# sensor_module_base.net
KiCad netlist of a schematic drawn in EAGLE
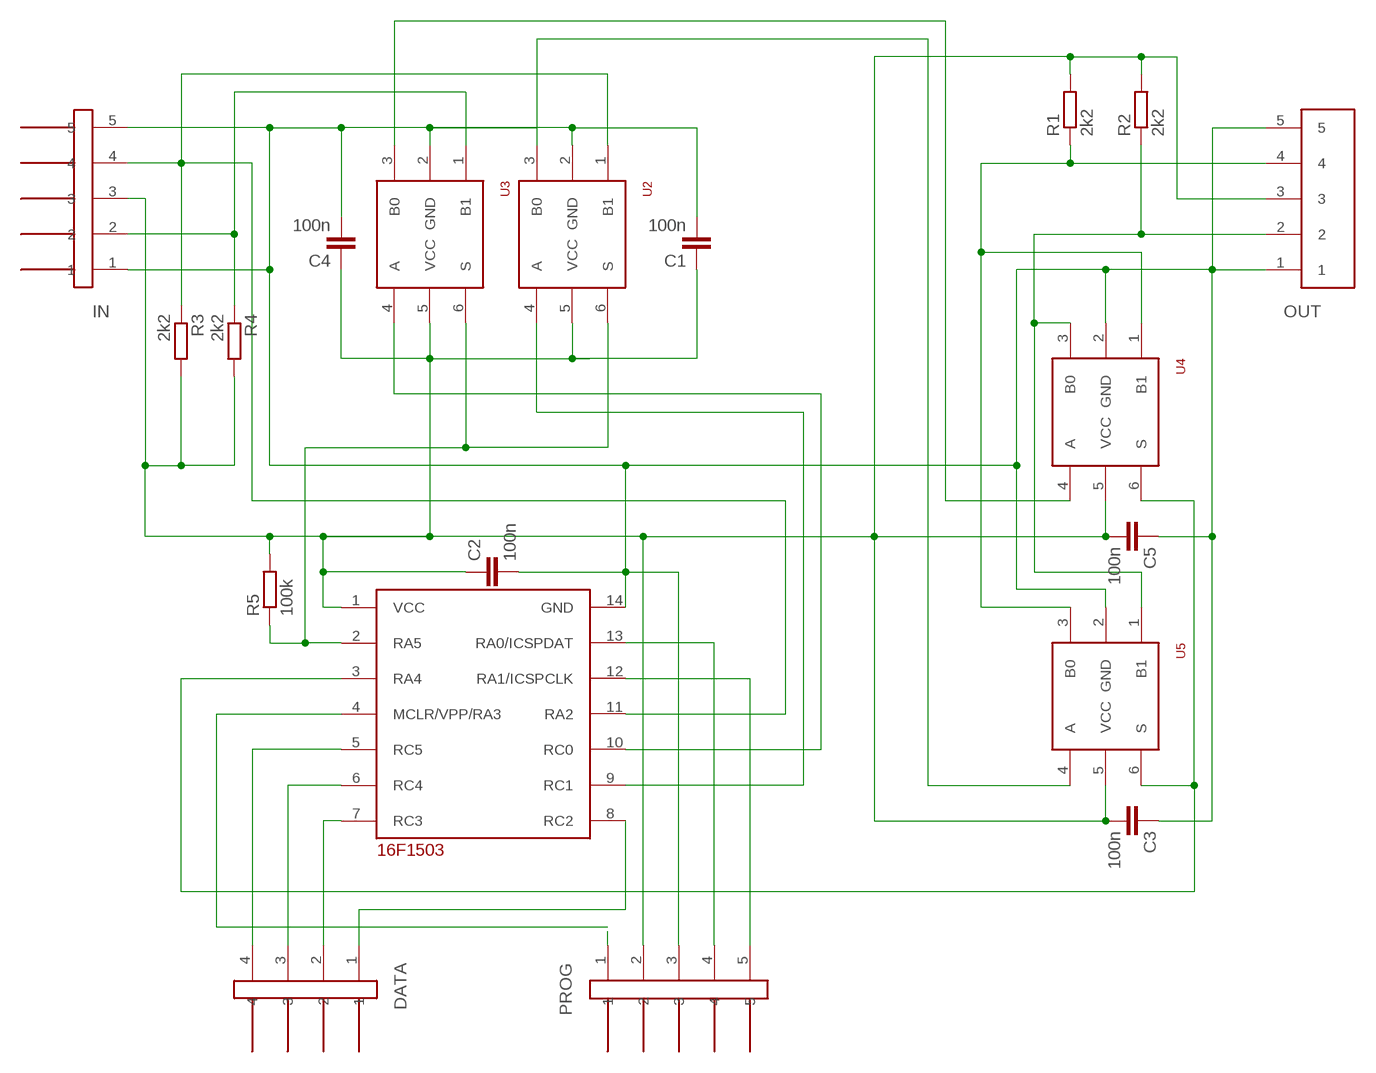
[diagram p0: schematic, sheet 1]

(export (version "E")
  (design (tool "Eeschema 10.0.6"))
  (components
    (comp (ref "C1")
      (value "100n")
      (footprint "eagle-import:C0603K")
      (libsource (lib "eagle-import") (part "C-EUC0603K"))
    )
    (comp (ref "C2")
      (value "100n")
      (footprint "eagle-import:C0603K")
      (libsource (lib "eagle-import") (part "C-EUC0603K"))
    )
    (comp (ref "C3")
      (value "100n")
      (footprint "eagle-import:C0603K")
      (libsource (lib "eagle-import") (part "C-EUC0603K"))
    )
    (comp (ref "C4")
      (value "100n")
      (footprint "eagle-import:C0603K")
      (libsource (lib "eagle-import") (part "C-EUC0603K"))
    )
    (comp (ref "C5")
      (value "100n")
      (footprint "eagle-import:C0603K")
      (libsource (lib "eagle-import") (part "C-EUC0603K"))
    )
    (comp (ref "DATA")
      (value "JUMPER4M")
      (footprint "eagle-import:JUMPER4M")
      (libsource (lib "eagle-import") (part "JUMPER4M"))
    )
    (comp (ref "IN")
      (value "JUMPER5M-90")
      (footprint "eagle-import:JUMPER5M-90")
      (libsource (lib "eagle-import") (part "JUMPER5M-90"))
    )
    (comp (ref "OUT")
      (value "JUMPER5F-90")
      (footprint "eagle-import:JUMPER5F-90")
      (libsource (lib "eagle-import") (part "JUMPER5F-90"))
    )
    (comp (ref "PROG")
      (value "JUMPER5M")
      (footprint "eagle-import:JUMPER5M")
      (libsource (lib "eagle-import") (part "JUMPER5M"))
    )
    (comp (ref "R1")
      (value "2k2")
      (footprint "eagle-import:R0603")
      (libsource (lib "eagle-import") (part "R-EU_R0603"))
    )
    (comp (ref "R2")
      (value "2k2")
      (footprint "eagle-import:R0603")
      (libsource (lib "eagle-import") (part "R-EU_R0603"))
    )
    (comp (ref "R3")
      (value "2k2")
      (footprint "eagle-import:R0603")
      (libsource (lib "eagle-import") (part "R-EU_R0603"))
    )
    (comp (ref "R4")
      (value "2k2")
      (footprint "eagle-import:R0603")
      (libsource (lib "eagle-import") (part "R-EU_R0603"))
    )
    (comp (ref "R5")
      (value "100k")
      (footprint "eagle-import:R0603")
      (libsource (lib "eagle-import") (part "R-EU_R0603"))
    )
    (comp (ref "U1")
      (value "16F1503")
      (footprint "eagle-import:TSSOP14")
      (libsource (lib "eagle-import") (part "16F103-TSSOP"))
    )
    (comp (ref "U2")
      (value "NC7SB3157P6X")
      (footprint "eagle-import:SC70-6L")
      (libsource (lib "eagle-import") (part "NC7SB3157P6X"))
    )
    (comp (ref "U3")
      (value "NC7SB3157P6X")
      (footprint "eagle-import:SC70-6L")
      (libsource (lib "eagle-import") (part "NC7SB3157P6X"))
    )
    (comp (ref "U4")
      (value "NC7SB3157P6X")
      (footprint "eagle-import:SC70-6L")
      (libsource (lib "eagle-import") (part "NC7SB3157P6X"))
    )
    (comp (ref "U5")
      (value "NC7SB3157P6X")
      (footprint "eagle-import:SC70-6L")
      (libsource (lib "eagle-import") (part "NC7SB3157P6X"))
    )
  )
  (nets
    (net (code "1") (name "Net-(U1-GND)") (class "Default")
      (node (ref "C1") (pin "2") (pinfunction "2_2") (pintype "passive"))
      (node (ref "C2") (pin "2") (pinfunction "2_2") (pintype "passive"))
      (node (ref "C3") (pin "1") (pinfunction "1_1") (pintype "passive"))
      (node (ref "C4") (pin "2") (pinfunction "2_2") (pintype "passive"))
      (node (ref "C5") (pin "1") (pinfunction "1_1") (pintype "passive"))
      (node (ref "IN") (pin "1") (pinfunction "1_1") (pintype "bidirectional"))
      (node (ref "IN") (pin "5") (pinfunction "5_5") (pintype "bidirectional"))
      (node (ref "OUT") (pin "1") (pinfunction "1_1") (pintype "bidirectional"))
      (node (ref "OUT") (pin "5") (pinfunction "5_5") (pintype "bidirectional"))
      (node (ref "PROG") (pin "3") (pinfunction "3_3") (pintype "bidirectional"))
      (node (ref "U1") (pin "14") (pinfunction "GND_14") (pintype "power_in"))
      (node (ref "U2") (pin "2") (pinfunction "GND_2") (pintype "power_in"))
      (node (ref "U3") (pin "2") (pinfunction "GND_2") (pintype "power_in"))
      (node (ref "U4") (pin "2") (pinfunction "GND_2") (pintype "power_in"))
      (node (ref "U5") (pin "2") (pinfunction "GND_2") (pintype "power_in"))
    )
    (net (code "2") (name "Net-(U1-MCLR{slash}VPP{slash}RA3)") (class "Default")
      (node (ref "PROG") (pin "1") (pinfunction "1_1") (pintype "bidirectional"))
      (node (ref "U1") (pin "4") (pinfunction "MCLR/VPP/RA3_4") (pintype "bidirectional"))
    )
    (net (code "3") (name "Net-(U1-RA0{slash}ICSPDAT)") (class "Default")
      (node (ref "PROG") (pin "4") (pinfunction "4_4") (pintype "bidirectional"))
      (node (ref "U1") (pin "13") (pinfunction "RA0/ICSPDAT_13") (pintype "bidirectional"))
    )
    (net (code "4") (name "Net-(U1-RA1{slash}ICSPCLK)") (class "Default")
      (node (ref "PROG") (pin "5") (pinfunction "5_5") (pintype "bidirectional"))
      (node (ref "U1") (pin "12") (pinfunction "RA1/ICSPCLK_12") (pintype "bidirectional"))
    )
    (net (code "5") (name "Net-(U1-RA2)") (class "Default")
      (node (ref "IN") (pin "4") (pinfunction "4_4") (pintype "bidirectional"))
      (node (ref "R3") (pin "1") (pinfunction "1_1") (pintype "passive"))
      (node (ref "U1") (pin "11") (pinfunction "RA2_11") (pintype "bidirectional"))
      (node (ref "U2") (pin "1") (pinfunction "B1_1") (pintype "bidirectional"))
    )
    (net (code "6") (name "Net-(U1-RA4)") (class "Default")
      (node (ref "U1") (pin "3") (pinfunction "RA4_3") (pintype "bidirectional"))
      (node (ref "U4") (pin "6") (pinfunction "S_6") (pintype "bidirectional"))
      (node (ref "U5") (pin "6") (pinfunction "S_6") (pintype "bidirectional"))
    )
    (net (code "7") (name "Net-(U1-RA5)") (class "Default")
      (node (ref "R5") (pin "1") (pinfunction "1_1") (pintype "passive"))
      (node (ref "U1") (pin "2") (pinfunction "RA5_2") (pintype "bidirectional"))
      (node (ref "U2") (pin "6") (pinfunction "S_6") (pintype "bidirectional"))
      (node (ref "U3") (pin "6") (pinfunction "S_6") (pintype "bidirectional"))
    )
    (net (code "8") (name "Net-(U1-RC0)") (class "Default")
      (node (ref "U1") (pin "10") (pinfunction "RC0_10") (pintype "bidirectional"))
      (node (ref "U3") (pin "4") (pinfunction "A_4") (pintype "bidirectional"))
    )
    (net (code "9") (name "Net-(U1-RC1)") (class "Default")
      (node (ref "U1") (pin "9") (pinfunction "RC1_9") (pintype "bidirectional"))
      (node (ref "U2") (pin "4") (pinfunction "A_4") (pintype "bidirectional"))
    )
    (net (code "10") (name "Net-(U1-RC2)") (class "Default")
      (node (ref "DATA") (pin "1") (pinfunction "1_1") (pintype "bidirectional"))
      (node (ref "U1") (pin "8") (pinfunction "RC2_8") (pintype "bidirectional"))
    )
    (net (code "11") (name "Net-(U1-RC3)") (class "Default")
      (node (ref "DATA") (pin "2") (pinfunction "2_2") (pintype "bidirectional"))
      (node (ref "U1") (pin "7") (pinfunction "RC3_7") (pintype "bidirectional"))
    )
    (net (code "12") (name "Net-(U1-RC4)") (class "Default")
      (node (ref "DATA") (pin "3") (pinfunction "3_3") (pintype "bidirectional"))
      (node (ref "U1") (pin "6") (pinfunction "RC4_6") (pintype "bidirectional"))
    )
    (net (code "13") (name "Net-(U1-RC5)") (class "Default")
      (node (ref "DATA") (pin "4") (pinfunction "4_4") (pintype "bidirectional"))
      (node (ref "U1") (pin "5") (pinfunction "RC5_5") (pintype "bidirectional"))
    )
    (net (code "14") (name "Net-(U1-VCC)") (class "Default")
      (node (ref "C1") (pin "1") (pinfunction "1_1") (pintype "passive"))
      (node (ref "C2") (pin "1") (pinfunction "1_1") (pintype "passive"))
      (node (ref "C3") (pin "2") (pinfunction "2_2") (pintype "passive"))
      (node (ref "C4") (pin "1") (pinfunction "1_1") (pintype "passive"))
      (node (ref "C5") (pin "2") (pinfunction "2_2") (pintype "passive"))
      (node (ref "IN") (pin "3") (pinfunction "3_3") (pintype "bidirectional"))
      (node (ref "OUT") (pin "3") (pinfunction "3_3") (pintype "bidirectional"))
      (node (ref "PROG") (pin "2") (pinfunction "2_2") (pintype "bidirectional"))
      (node (ref "R1") (pin "2") (pinfunction "2_2") (pintype "passive"))
      (node (ref "R2") (pin "2") (pinfunction "2_2") (pintype "passive"))
      (node (ref "R3") (pin "2") (pinfunction "2_2") (pintype "passive"))
      (node (ref "R4") (pin "2") (pinfunction "2_2") (pintype "passive"))
      (node (ref "R5") (pin "2") (pinfunction "2_2") (pintype "passive"))
      (node (ref "U1") (pin "1") (pinfunction "VCC_1") (pintype "power_in"))
      (node (ref "U2") (pin "5") (pinfunction "VCC_5") (pintype "power_in"))
      (node (ref "U3") (pin "5") (pinfunction "VCC_5") (pintype "power_in"))
      (node (ref "U4") (pin "5") (pinfunction "VCC_5") (pintype "power_in"))
      (node (ref "U5") (pin "5") (pinfunction "VCC_5") (pintype "power_in"))
    )
    (net (code "15") (name "Net-(U2-B0)") (class "Default")
      (node (ref "U2") (pin "3") (pinfunction "B0_3") (pintype "bidirectional"))
      (node (ref "U5") (pin "4") (pinfunction "A_4") (pintype "bidirectional"))
    )
    (net (code "16") (name "Net-(U3-B0)") (class "Default")
      (node (ref "U3") (pin "3") (pinfunction "B0_3") (pintype "bidirectional"))
      (node (ref "U4") (pin "4") (pinfunction "A_4") (pintype "bidirectional"))
    )
    (net (code "17") (name "Net-(U3-B1)") (class "Default")
      (node (ref "IN") (pin "2") (pinfunction "2_2") (pintype "bidirectional"))
      (node (ref "R4") (pin "1") (pinfunction "1_1") (pintype "passive"))
      (node (ref "U3") (pin "1") (pinfunction "B1_1") (pintype "bidirectional"))
    )
    (net (code "18") (name "Net-(U4-B0)") (class "Default")
      (node (ref "OUT") (pin "2") (pinfunction "2_2") (pintype "bidirectional"))
      (node (ref "R2") (pin "1") (pinfunction "1_1") (pintype "passive"))
      (node (ref "U4") (pin "3") (pinfunction "B0_3") (pintype "bidirectional"))
      (node (ref "U5") (pin "1") (pinfunction "B1_1") (pintype "bidirectional"))
    )
    (net (code "19") (name "Net-(U4-B1)") (class "Default")
      (node (ref "OUT") (pin "4") (pinfunction "4_4") (pintype "bidirectional"))
      (node (ref "R1") (pin "1") (pinfunction "1_1") (pintype "passive"))
      (node (ref "U4") (pin "1") (pinfunction "B1_1") (pintype "bidirectional"))
      (node (ref "U5") (pin "3") (pinfunction "B0_3") (pintype "bidirectional"))
    )
  )
)
